# SCH_AIS-PBL-2_0_2025-09-11.net
KiCad netlist of a schematic drawn in EasyEDA
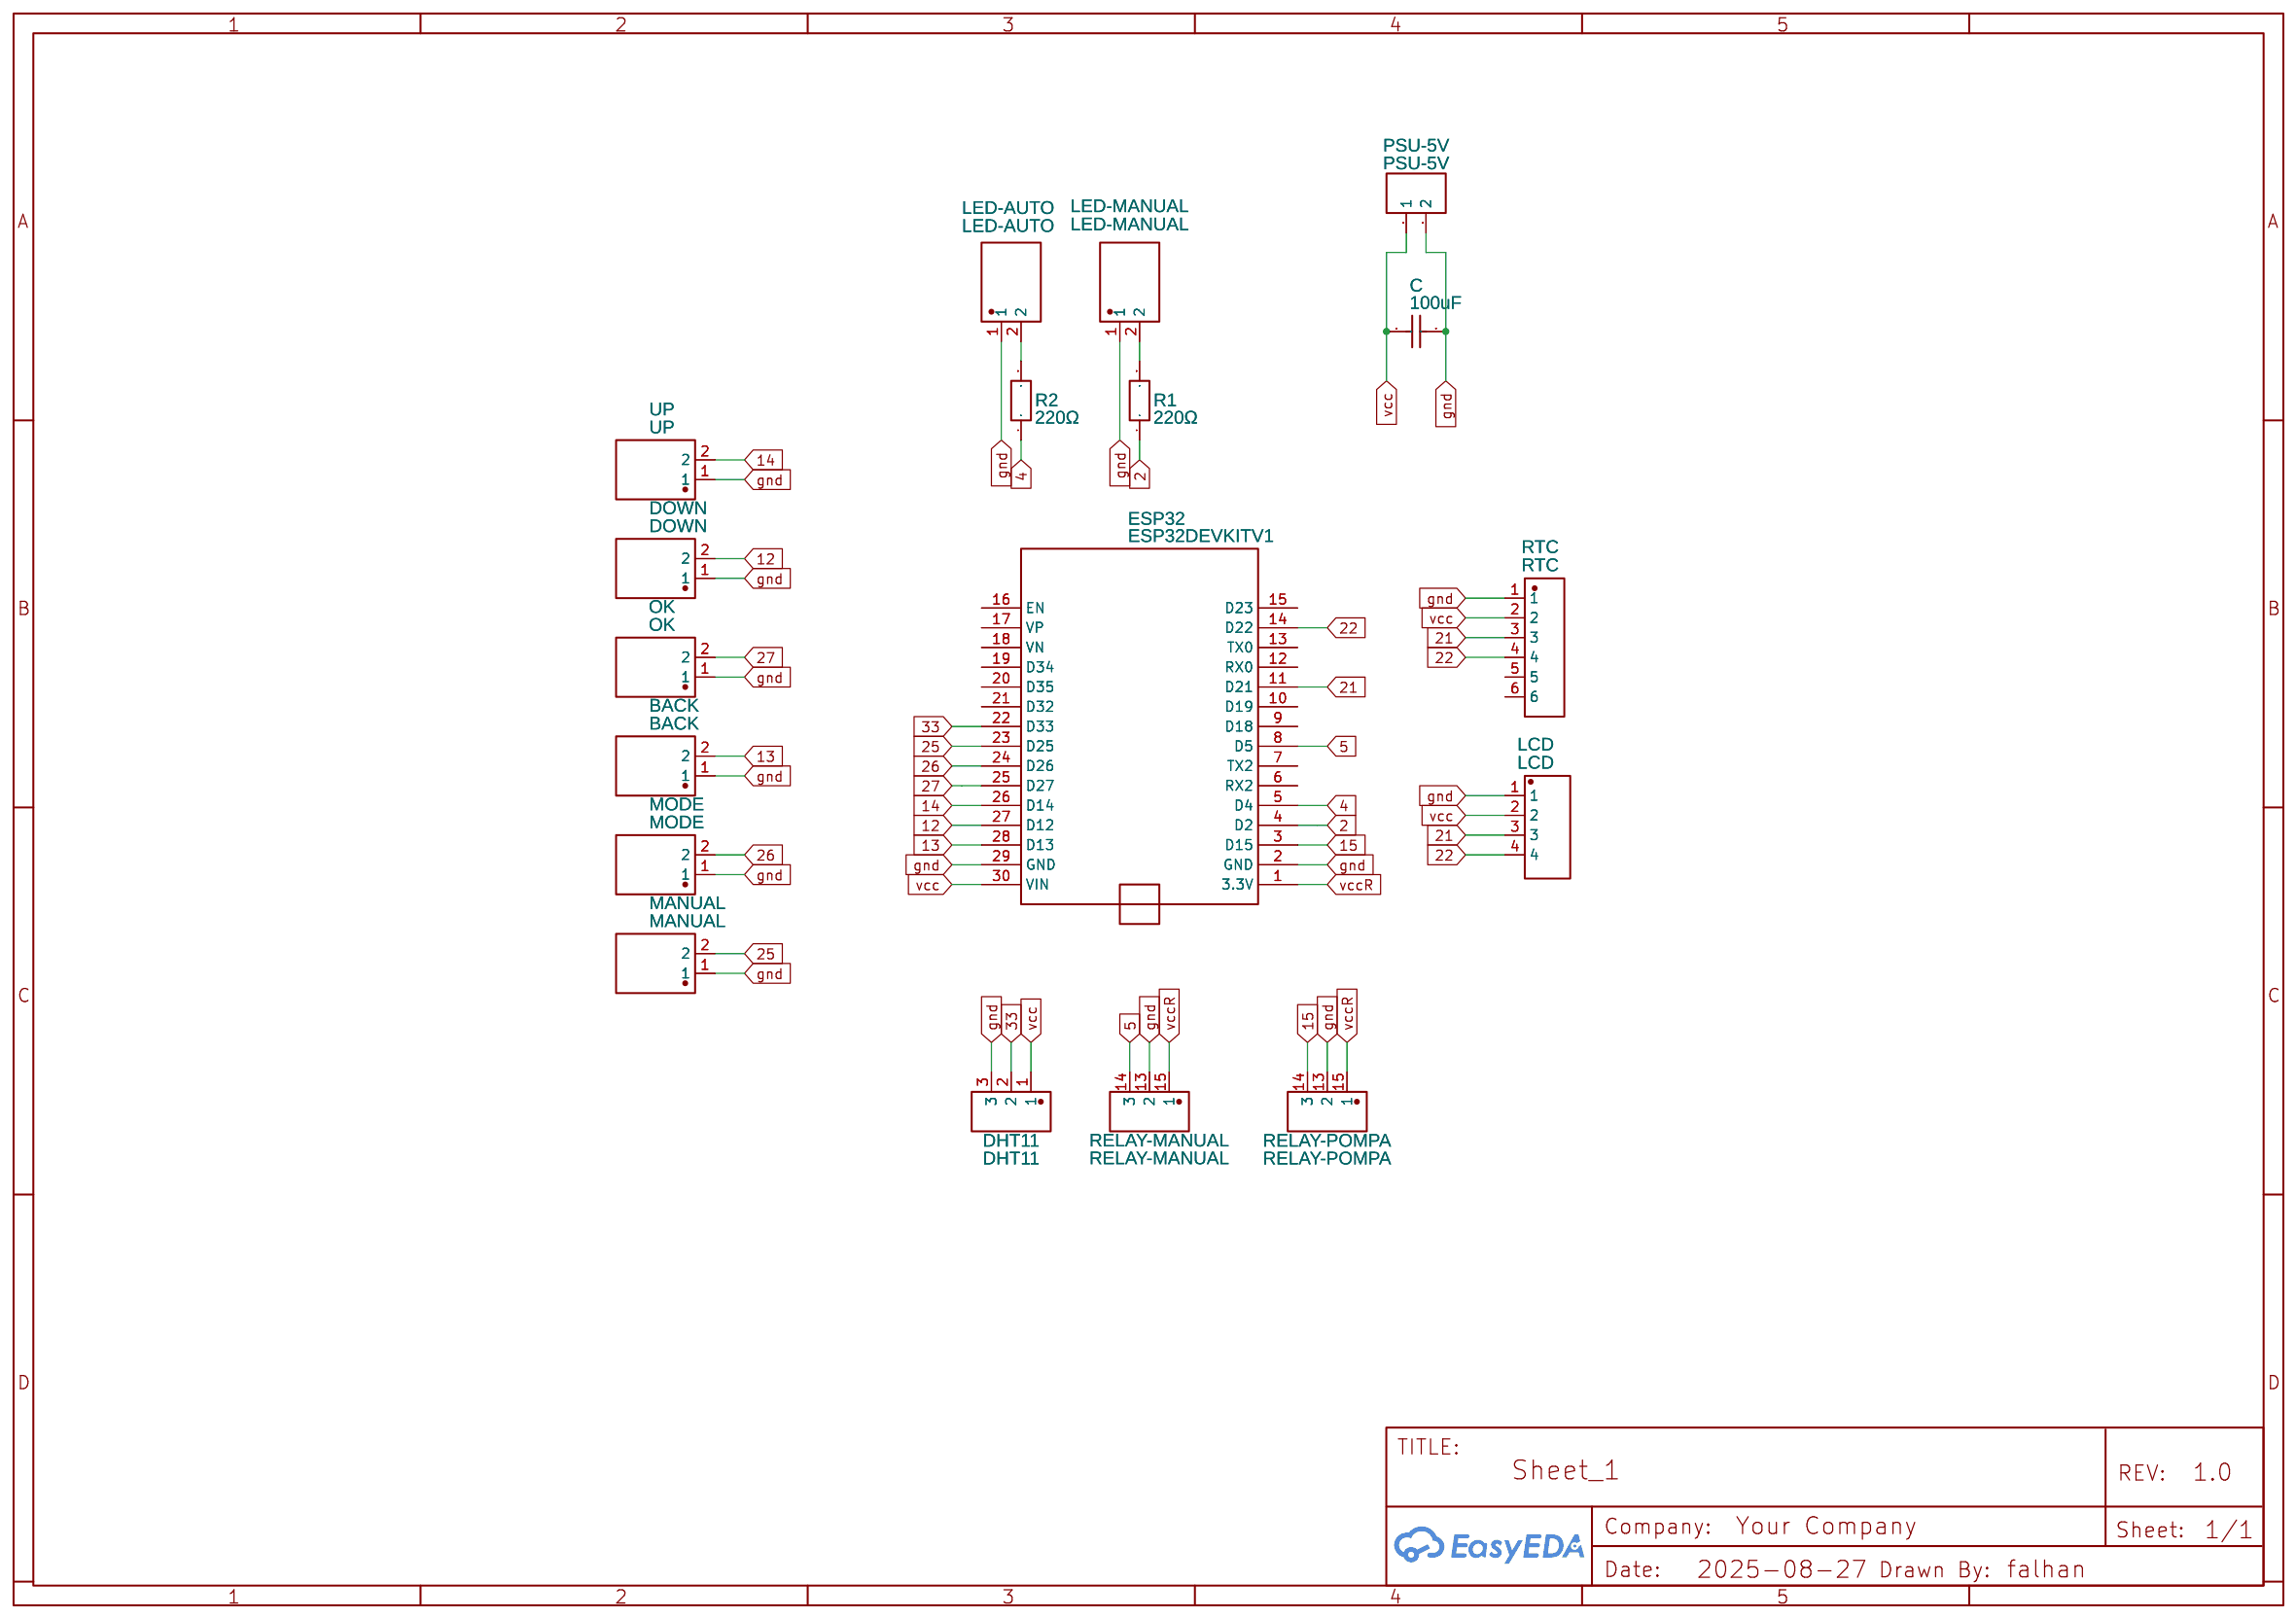
[diagram p0: schematic sheet]

(export (version "E")
  (design (tool "Eeschema 10.0.6"))
  (components
    (comp (ref "BACK")
      (value "BACK")
      (fields (field (name "Manufacturer Part") "W-2501S02P-K200") (field (name "Manufacturer") "Ckmtw(灿科盟)"))
      (libsource (lib "") (part "2501S-2P_C168996_5"))
    )
    (comp (ref "C")
      (value "100uF")
      (fields
        (field (name "Manufacturer Part") "1nF ±20% 250V/AC Y2Capacitor")
        (field (name "Manufacturer") "ReliaPro")
      )
      (libsource (lib "") (part "1nF ±20% 250V/AC Y2Capacitor"))
    )
    (comp (ref "DHT11")
      (value "DHT11")
      (fields
        (field (name "Manufacturer Part") "ZX-XH2.54-3PZZ")
        (field (name "Manufacturer") "Megastar(兆星)")
      )
      (libsource (lib "") (part "ZX-XH2.54-3PZZ"))
    )
    (comp (ref "DOWN")
      (value "DOWN")
      (fields (field (name "Manufacturer Part") "W-2501S02P-K200") (field (name "Manufacturer") "Ckmtw(灿科盟)"))
      (libsource (lib "") (part "2501S-2P_C168996_4"))
    )
    (comp (ref "ESP32") (value "ESP32DEVKITV1") (libsource (lib "") (part "ESP32DEVKITV1")))
    (comp (ref "LCD")
      (value "LCD")
      (fields (field (name "Manufacturer Part") "W-2501S04P-K000") (field (name "Manufacturer") "Ckmtw(灿科盟)"))
      (libsource (lib "") (part "2501S-4P_C125328"))
    )
    (comp (ref "LED-AUTO")
      (value "LED-AUTO")
      (fields (field (name "Manufacturer Part") "W-2501S02P-K200") (field (name "Manufacturer") "Ckmtw(灿科盟)"))
      (libsource (lib "") (part "2501S-2P_C168996_2"))
    )
    (comp (ref "LED-MANUAL")
      (value "LED-MANUAL")
      (fields (field (name "Manufacturer Part") "W-2501S02P-K200") (field (name "Manufacturer") "Ckmtw(灿科盟)"))
      (libsource (lib "") (part "2501S-2P_C168996_6"))
    )
    (comp (ref "MANUAL")
      (value "MANUAL")
      (fields (field (name "Manufacturer Part") "W-2501S02P-K200") (field (name "Manufacturer") "Ckmtw(灿科盟)"))
      (libsource (lib "") (part "2501S-2P_C168996_1"))
    )
    (comp (ref "MODE")
      (value "MODE")
      (fields (field (name "Manufacturer Part") "W-2501S02P-K200") (field (name "Manufacturer") "Ckmtw(灿科盟)"))
      (libsource (lib "") (part "2501S-2P_C168996"))
    )
    (comp (ref "OK")
      (value "OK")
      (fields (field (name "Manufacturer Part") "W-2501S02P-K200") (field (name "Manufacturer") "Ckmtw(灿科盟)"))
      (libsource (lib "") (part "2501S-2P_C168996_3"))
    )
    (comp (ref "PSU-5V") (value "PSU-5V") (libsource (lib "") (part "CONN-TH_2P-P5.00")))
    (comp (ref "R1")
      (value "220Ω")
      (fields
        (field (name "Manufacturer Part") "RN1/4W10KFT/BA1")
        (field (name "Manufacturer") "Tyohm(幸亚电阻)")
      )
      (libsource (lib "") (part "RN 1/4W 10K F T/B A1"))
    )
    (comp (ref "R2")
      (value "220Ω")
      (fields
        (field (name "Manufacturer Part") "RN1/4W10KFT/BA1")
        (field (name "Manufacturer") "Tyohm(幸亚电阻)")
      )
      (libsource (lib "") (part "RN 1/4W 10K F T/B A1"))
    )
    (comp (ref "RELAY-MANUAL")
      (value "RELAY-MANUAL")
      (fields
        (field (name "Manufacturer Part") "ZX-XH2.54-3PZZ")
        (field (name "Manufacturer") "Megastar(兆星)")
      )
      (libsource (lib "") (part "ZX-XH2.54-3PZZ_1"))
    )
    (comp (ref "RELAY-POMPA")
      (value "RELAY-POMPA")
      (fields
        (field (name "Manufacturer Part") "ZX-XH2.54-3PZZ")
        (field (name "Manufacturer") "Megastar(兆星)")
      )
      (libsource (lib "") (part "ZX-XH2.54-3PZZ_2"))
    )
    (comp (ref "RTC")
      (value "RTC")
      (fields (field (name "Manufacturer Part") "2.54-1*6P母") (field (name "Manufacturer") "BOOMELE(博穆精密)"))
      (libsource (lib "") (part "Header-Female-2.54_1x6"))
    )
    (comp (ref "UP")
      (value "UP")
      (fields (field (name "Manufacturer Part") "W-2501S02P-K200") (field (name "Manufacturer") "Ckmtw(灿科盟)"))
      (libsource (lib "") (part "2501S-2P_C168996_7"))
    )
  )
  (nets
    (net (code "1") (name "2") (class "Default")
      (node (ref "ESP32") (pin "4") (pinfunction "D2_4") (pintype "unspecified"))
      (node (ref "R1") (pin "1") (pinfunction "1_1") (pintype "unspecified"))
    )
    (net (code "2") (name "4") (class "Default")
      (node (ref "ESP32") (pin "5") (pinfunction "D4_5") (pintype "unspecified"))
      (node (ref "R2") (pin "1") (pinfunction "1_1") (pintype "unspecified"))
    )
    (net (code "3") (name "5") (class "Default")
      (node (ref "ESP32") (pin "8") (pinfunction "D5_8") (pintype "unspecified"))
      (node (ref "RELAY-MANUAL") (pin "14") (pinfunction "3_14") (pintype "unspecified"))
    )
    (net (code "4") (name "12") (class "Default")
      (node (ref "DOWN") (pin "2") (pinfunction "2_2") (pintype "unspecified"))
      (node (ref "ESP32") (pin "27") (pinfunction "D12_27") (pintype "unspecified"))
    )
    (net (code "5") (name "13") (class "Default")
      (node (ref "BACK") (pin "2") (pinfunction "2_2") (pintype "unspecified"))
      (node (ref "ESP32") (pin "28") (pinfunction "D13_28") (pintype "unspecified"))
    )
    (net (code "6") (name "14") (class "Default")
      (node (ref "ESP32") (pin "26") (pinfunction "D14_26") (pintype "unspecified"))
      (node (ref "UP") (pin "2") (pinfunction "2_2") (pintype "unspecified"))
    )
    (net (code "7") (name "15") (class "Default")
      (node (ref "ESP32") (pin "3") (pinfunction "D15_3") (pintype "unspecified"))
      (node (ref "RELAY-POMPA") (pin "14") (pinfunction "3_14") (pintype "unspecified"))
    )
    (net (code "8") (name "21") (class "Default")
      (node (ref "ESP32") (pin "11") (pinfunction "D21_11") (pintype "unspecified"))
      (node (ref "LCD") (pin "3") (pinfunction "3_3") (pintype "unspecified"))
      (node (ref "RTC") (pin "3") (pinfunction "3_3") (pintype "unspecified"))
    )
    (net (code "9") (name "22") (class "Default")
      (node (ref "ESP32") (pin "14") (pinfunction "D22_14") (pintype "unspecified"))
      (node (ref "LCD") (pin "4") (pinfunction "4_4") (pintype "unspecified"))
      (node (ref "RTC") (pin "4") (pinfunction "4_4") (pintype "unspecified"))
    )
    (net (code "10") (name "25") (class "Default")
      (node (ref "ESP32") (pin "23") (pinfunction "D25_23") (pintype "unspecified"))
      (node (ref "MANUAL") (pin "2") (pinfunction "2_2") (pintype "unspecified"))
    )
    (net (code "11") (name "26") (class "Default")
      (node (ref "ESP32") (pin "24") (pinfunction "D26_24") (pintype "unspecified"))
      (node (ref "MODE") (pin "2") (pinfunction "2_2") (pintype "unspecified"))
    )
    (net (code "12") (name "27") (class "Default")
      (node (ref "ESP32") (pin "25") (pinfunction "D27_25") (pintype "unspecified"))
      (node (ref "OK") (pin "2") (pinfunction "2_2") (pintype "unspecified"))
    )
    (net (code "13") (name "33") (class "Default")
      (node (ref "DHT11") (pin "2") (pinfunction "2_2") (pintype "unspecified"))
      (node (ref "ESP32") (pin "22") (pinfunction "D33_22") (pintype "unspecified"))
    )
    (net (code "14") (name "Net-(LED-AUTO-Pad2)") (class "Default")
      (node (ref "LED-AUTO") (pin "2") (pinfunction "2_2") (pintype "unspecified"))
      (node (ref "R2") (pin "2") (pinfunction "2_2") (pintype "unspecified"))
    )
    (net (code "15") (name "Net-(LED-MANUAL-Pad2)") (class "Default")
      (node (ref "LED-MANUAL") (pin "2") (pinfunction "2_2") (pintype "unspecified"))
      (node (ref "R1") (pin "2") (pinfunction "2_2") (pintype "unspecified"))
    )
    (net (code "16") (name "gnd") (class "Default")
      (node (ref "BACK") (pin "1") (pinfunction "1_1") (pintype "unspecified"))
      (node (ref "C") (pin "2") (pinfunction "1_2") (pintype "input"))
      (node (ref "DHT11") (pin "3") (pinfunction "3_3") (pintype "unspecified"))
      (node (ref "DOWN") (pin "1") (pinfunction "1_1") (pintype "unspecified"))
      (node (ref "ESP32") (pin "2") (pinfunction "GND_2") (pintype "unspecified"))
      (node (ref "ESP32") (pin "29") (pinfunction "GND_29") (pintype "unspecified"))
      (node (ref "LCD") (pin "1") (pinfunction "1_1") (pintype "unspecified"))
      (node (ref "LED-AUTO") (pin "1") (pinfunction "1_1") (pintype "unspecified"))
      (node (ref "LED-MANUAL") (pin "1") (pinfunction "1_1") (pintype "unspecified"))
      (node (ref "MANUAL") (pin "1") (pinfunction "1_1") (pintype "unspecified"))
      (node (ref "MODE") (pin "1") (pinfunction "1_1") (pintype "unspecified"))
      (node (ref "OK") (pin "1") (pinfunction "1_1") (pintype "unspecified"))
      (node (ref "PSU-5V") (pin "2") (pinfunction "2_2") (pintype "unspecified"))
      (node (ref "RELAY-MANUAL") (pin "13") (pinfunction "2_13") (pintype "unspecified"))
      (node (ref "RELAY-POMPA") (pin "13") (pinfunction "2_13") (pintype "unspecified"))
      (node (ref "RTC") (pin "1") (pinfunction "1_1") (pintype "unspecified"))
      (node (ref "UP") (pin "1") (pinfunction "1_1") (pintype "unspecified"))
    )
    (net (code "17") (name "unconnected-(ESP32-D18-Pad9)") (class "Default")
      (node (ref "ESP32") (pin "9") (pinfunction "D18_9") (pintype "unspecified"))
    )
    (net (code "18") (name "unconnected-(ESP32-D19-Pad10)") (class "Default")
      (node (ref "ESP32") (pin "10") (pinfunction "D19_10") (pintype "unspecified"))
    )
    (net (code "19") (name "unconnected-(ESP32-D23-Pad15)") (class "Default")
      (node (ref "ESP32") (pin "15") (pinfunction "D23_15") (pintype "unspecified"))
    )
    (net (code "20") (name "unconnected-(ESP32-D32-Pad21)") (class "Default")
      (node (ref "ESP32") (pin "21") (pinfunction "D32_21") (pintype "unspecified"))
    )
    (net (code "21") (name "unconnected-(ESP32-D34-Pad19)") (class "Default")
      (node (ref "ESP32") (pin "19") (pinfunction "D34_19") (pintype "unspecified"))
    )
    (net (code "22") (name "unconnected-(ESP32-D35-Pad20)") (class "Default")
      (node (ref "ESP32") (pin "20") (pinfunction "D35_20") (pintype "unspecified"))
    )
    (net (code "23") (name "unconnected-(ESP32-EN-Pad16)") (class "Default")
      (node (ref "ESP32") (pin "16") (pinfunction "EN_16") (pintype "unspecified"))
    )
    (net (code "24") (name "unconnected-(ESP32-RX0-Pad12)") (class "Default")
      (node (ref "ESP32") (pin "12") (pinfunction "RX0_12") (pintype "unspecified"))
    )
    (net (code "25") (name "unconnected-(ESP32-RX2-Pad6)") (class "Default")
      (node (ref "ESP32") (pin "6") (pinfunction "RX2_6") (pintype "unspecified"))
    )
    (net (code "26") (name "unconnected-(ESP32-TX0-Pad13)") (class "Default")
      (node (ref "ESP32") (pin "13") (pinfunction "TX0_13") (pintype "unspecified"))
    )
    (net (code "27") (name "unconnected-(ESP32-TX2-Pad7)") (class "Default")
      (node (ref "ESP32") (pin "7") (pinfunction "TX2_7") (pintype "unspecified"))
    )
    (net (code "28") (name "unconnected-(ESP32-VN-Pad18)") (class "Default")
      (node (ref "ESP32") (pin "18") (pinfunction "VN_18") (pintype "unspecified"))
    )
    (net (code "29") (name "unconnected-(ESP32-VP-Pad17)") (class "Default")
      (node (ref "ESP32") (pin "17") (pinfunction "VP_17") (pintype "unspecified"))
    )
    (net (code "30") (name "unconnected-(RTC-Pad5)") (class "Default")
      (node (ref "RTC") (pin "5") (pinfunction "5_5") (pintype "unspecified"))
    )
    (net (code "31") (name "unconnected-(RTC-Pad6)") (class "Default")
      (node (ref "RTC") (pin "6") (pinfunction "6_6") (pintype "unspecified"))
    )
    (net (code "32") (name "vcc") (class "Default")
      (node (ref "C") (pin "1") (pinfunction "2_1") (pintype "input"))
      (node (ref "DHT11") (pin "1") (pinfunction "1_1") (pintype "unspecified"))
      (node (ref "ESP32") (pin "30") (pinfunction "VIN_30") (pintype "unspecified"))
      (node (ref "LCD") (pin "2") (pinfunction "2_2") (pintype "unspecified"))
      (node (ref "PSU-5V") (pin "1") (pinfunction "1_1") (pintype "unspecified"))
      (node (ref "RTC") (pin "2") (pinfunction "2_2") (pintype "unspecified"))
    )
    (net (code "33") (name "vccR") (class "Default")
      (node (ref "ESP32") (pin "1") (pinfunction "3.3V_1") (pintype "unspecified"))
      (node (ref "RELAY-MANUAL") (pin "15") (pinfunction "1_15") (pintype "unspecified"))
      (node (ref "RELAY-POMPA") (pin "15") (pinfunction "1_15") (pintype "unspecified"))
    )
  )
)
